# 917S001_ZHTH-010_-F.net
KiCad netlist of a schematic drawn in Altium Designer
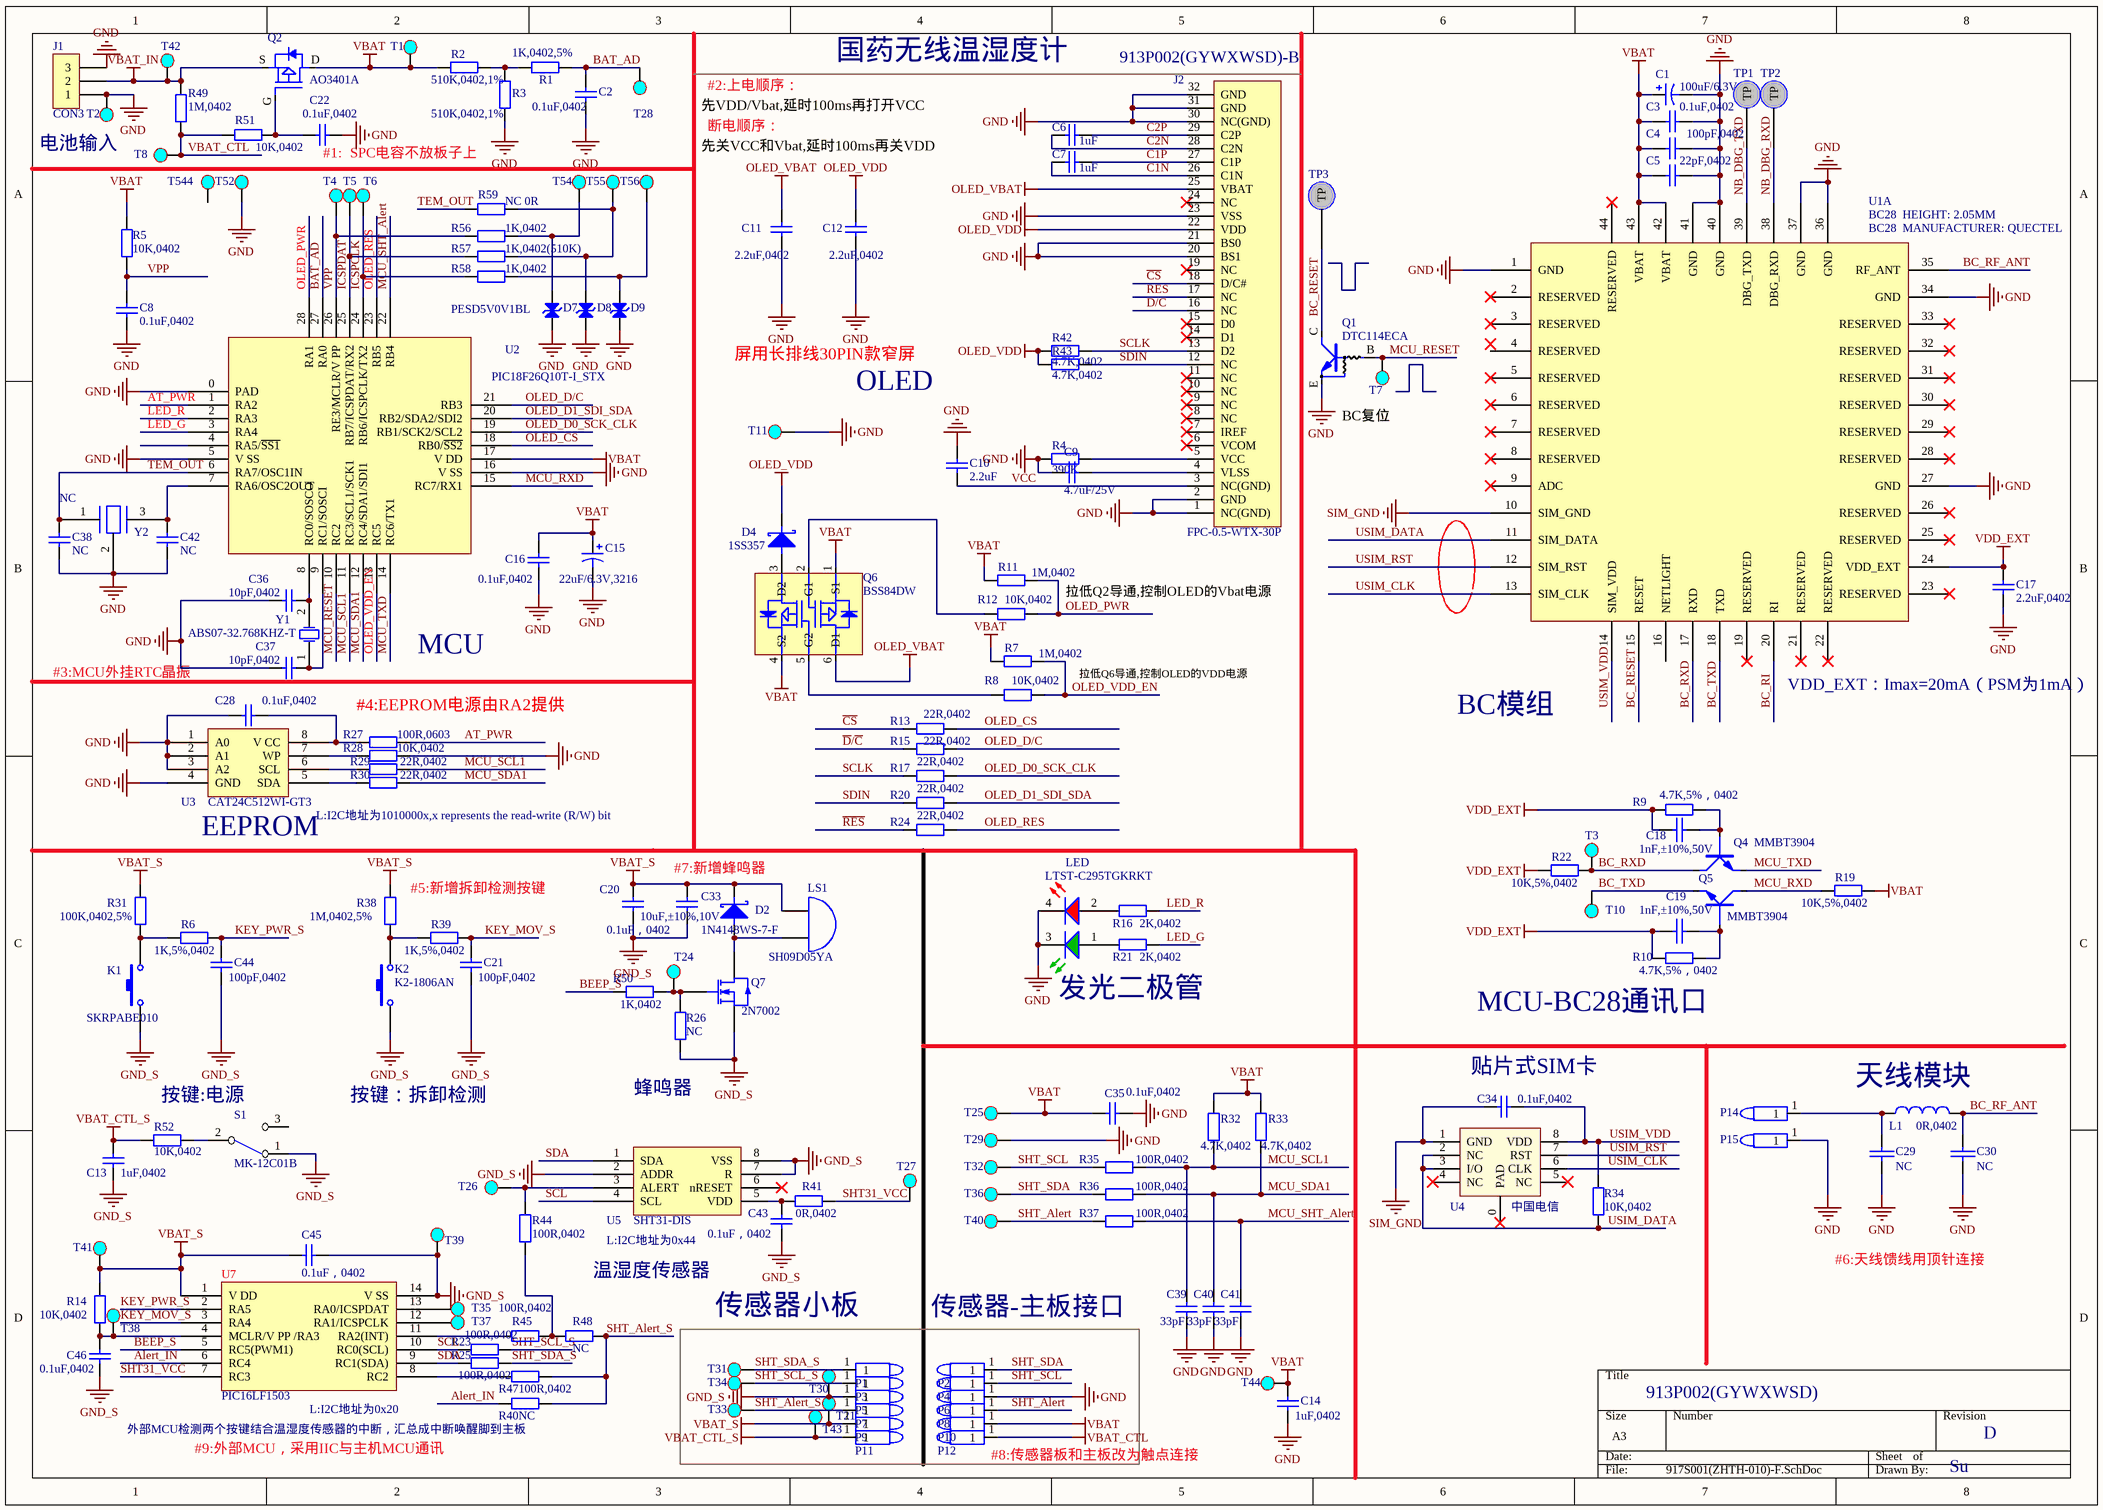
[diagram p0: 917S001(ZHTH-010)-F.SchDoc]

(export (version "E")
  (design (tool "Eeschema 10.0.6"))
  (components
    (comp (ref "C1")
      (value "100uF/6.3V")
      (footprint "3528")
      (description "Polarized Capacitor (Axial)")
      (fields (field (name "PUBLISHER") "Altium Limited"))
      (libsource (lib "JL_SCH") (part "Cap Pol2"))
    )
    (comp (ref "C2")
      (value "0.1uF,0402")
      (footprint "0402")
      (description "Capacitor")
      (fields (field (name "PUBLISHER") "Altium Limited"))
      (libsource (lib "*") (part "Cap"))
    )
    (comp (ref "C3")
      (value "0.1uF,0402")
      (footprint "0402")
      (description "Capacitor")
      (fields (field (name "PUBLISHER") "Altium Limited"))
      (libsource (lib "*") (part "Cap"))
    )
    (comp (ref "C4")
      (value "100pF,0402")
      (footprint "0402")
      (description "Capacitor")
      (fields (field (name "PUBLISHER") "Altium Limited"))
      (libsource (lib "*") (part "Cap"))
    )
    (comp (ref "C5")
      (value "22pF,0402")
      (footprint "0402")
      (description "Capacitor")
      (fields (field (name "PUBLISHER") "Altium Limited"))
      (libsource (lib "*") (part "Cap"))
    )
    (comp (ref "C6")
      (value "1uF")
      (footprint "0402")
      (description "Capacitor")
      (libsource (lib "JL_SCH") (part "Cap"))
    )
    (comp (ref "C7")
      (value "1uF")
      (footprint "0402")
      (description "Capacitor")
      (libsource (lib "JL_SCH") (part "Cap"))
    )
    (comp (ref "C8")
      (value "0.1uF,0402")
      (footprint "0402")
      (description "Capacitor")
      (fields (field (name "PUBLISHER") "Altium Limited"))
      (libsource (lib "*") (part "Cap"))
    )
    (comp (ref "C9")
      (value "4.7uF/25V")
      (footprint "0805")
      (description "Capacitor")
      (libsource (lib "JL_SCH") (part "Cap"))
    )
    (comp (ref "C10")
      (value "2.2uF")
      (footprint "0402")
      (description "Capacitor")
      (libsource (lib "JL_SCH") (part "Cap"))
    )
    (comp (ref "C11")
      (value "2.2uF,0402")
      (footprint "0402")
      (description "Capacitor")
      (libsource (lib "JL_SCH") (part "Cap"))
    )
    (comp (ref "C12")
      (value "2.2uF,0402")
      (footprint "0402")
      (description "Capacitor")
      (libsource (lib "JL_SCH") (part "Cap"))
    )
    (comp (ref "C13")
      (value "1uF,0402")
      (footprint "0402")
      (description "Capacitor")
      (libsource (lib "Miscellaneous Devices") (part "Cap"))
    )
    (comp (ref "C14")
      (value "1uF,0402")
      (footprint "0402")
      (description "Capacitor")
      (libsource (lib "Miscellaneous Devices") (part "Cap"))
    )
    (comp (ref "C15")
      (value "22uF/6.3V,3216")
      (footprint "3216")
      (description "Polarized Capacitor (Axial)")
      (fields (field (name "PUBLISHER") "Altium Limited"))
      (libsource (lib "JL_SCH") (part "Cap Pol2"))
    )
    (comp (ref "C16")
      (value "0.1uF,0402")
      (footprint "0402")
      (description "Capacitor")
      (fields (field (name "PUBLISHER") "Altium Limited"))
      (libsource (lib "*") (part "Cap"))
    )
    (comp (ref "C17")
      (value "2.2uF,0402")
      (footprint "0402")
      (description "Capacitor")
      (fields (field (name "PUBLISHER") "Altium Limited"))
      (libsource (lib "*") (part "Cap"))
    )
    (comp (ref "C18")
      (value "1nF,±10%,50V")
      (footprint "0402")
      (description "Capacitor")
      (fields
        (field (name "MANUFACTURER") "Generic Components")
        (field (name "PUBLISHER") "Altium Hobart Technology Centre")
      )
      (libsource (lib "LSD_DXPlib") (part "Cap"))
    )
    (comp (ref "C19")
      (value "1nF,±10%,50V")
      (footprint "0402")
      (description "Capacitor")
      (fields
        (field (name "MANUFACTURER") "Generic Components")
        (field (name "PUBLISHER") "Altium Hobart Technology Centre")
      )
      (libsource (lib "LSD_DXPlib") (part "Cap"))
    )
    (comp (ref "C20")
      (value "0.1uF，0402")
      (footprint "0402")
      (description "Capacitor")
      (fields (field (name "PUBLISHER") "Altium Limited"))
      (libsource (lib "*") (part "Cap"))
    )
    (comp (ref "C21")
      (value "100pF,0402")
      (footprint "0402")
      (description "Capacitor")
      (libsource (lib "Miscellaneous Devices") (part "Cap"))
    )
    (comp (ref "C22")
      (value "0.1uF,0402")
      (footprint "0402")
      (description "Capacitor")
      (fields (field (name "PUBLISHER") "Altium Limited"))
      (libsource (lib "*") (part "Cap"))
    )
    (comp (ref "C28")
      (value "0.1uF,0402")
      (footprint "0402")
      (description "Capacitor")
      (fields (field (name "PUBLISHER") "Altium Limited"))
      (libsource (lib "*") (part "Cap"))
    )
    (comp (ref "C29")
      (value "NC")
      (footprint "0402")
      (description "Capacitor")
      (fields
        (field (name "MANUFACTURER") "Generic Components")
        (field (name "PUBLISHER") "Altium Hobart Technology Centre")
      )
      (libsource (lib "LSD_DXPlib") (part "Cap"))
    )
    (comp (ref "C30")
      (value "NC")
      (footprint "0402")
      (description "Capacitor")
      (fields
        (field (name "MANUFACTURER") "Generic Components")
        (field (name "PUBLISHER") "Altium Hobart Technology Centre")
      )
      (libsource (lib "LSD_DXPlib") (part "Cap"))
    )
    (comp (ref "C33")
      (value "10uF,±10%,10V")
      (footprint "0805")
      (description "Capacitor")
      (libsource (lib "JL_SCH") (part "Cap"))
    )
    (comp (ref "C34")
      (value "0.1uF,0402")
      (footprint "0402")
      (description "Capacitor")
      (fields (field (name "PUBLISHER") "Altium Limited"))
      (libsource (lib "Miscellaneous Devices") (part "Cap"))
    )
    (comp (ref "C35")
      (value "0.1uF,0402")
      (footprint "0402")
      (description "Capacitor")
      (fields (field (name "PUBLISHER") "Altium Limited"))
      (libsource (lib "*") (part "Cap"))
    )
    (comp (ref "C36")
      (value "10pF,0402")
      (footprint "0402")
      (description "Capacitor")
      (fields (field (name "PUBLISHER") "Altium Limited"))
      (libsource (lib "*") (part "Cap"))
    )
    (comp (ref "C37")
      (value "10pF,0402")
      (footprint "0402")
      (description "Capacitor")
      (fields (field (name "PUBLISHER") "Altium Limited"))
      (libsource (lib "*") (part "Cap"))
    )
    (comp (ref "C38")
      (value "NC")
      (footprint "0402")
      (description "Capacitor")
      (fields (field (name "PUBLISHER") "Altium Limited"))
      (libsource (lib "*") (part "Cap"))
    )
    (comp (ref "C39")
      (value "33pF")
      (footprint "0402")
      (description "Capacitor")
      (fields (field (name "PUBLISHER") "Altium Limited"))
      (libsource (lib "Miscellaneous Devices") (part "Cap"))
    )
    (comp (ref "C40")
      (value "33pF")
      (footprint "0402")
      (description "Capacitor")
      (fields (field (name "PUBLISHER") "Altium Limited"))
      (libsource (lib "Miscellaneous Devices") (part "Cap"))
    )
    (comp (ref "C41")
      (value "33pF")
      (footprint "0402")
      (description "Capacitor")
      (fields (field (name "PUBLISHER") "Altium Limited"))
      (libsource (lib "Miscellaneous Devices") (part "Cap"))
    )
    (comp (ref "C42")
      (value "NC")
      (footprint "0402")
      (description "Capacitor")
      (fields (field (name "PUBLISHER") "Altium Limited"))
      (libsource (lib "*") (part "Cap"))
    )
    (comp (ref "C43")
      (value "0.1uF，0402")
      (footprint "0402")
      (description "Capacitor")
      (fields (field (name "PUBLISHER") "Altium Limited"))
      (libsource (lib "*") (part "Cap"))
    )
    (comp (ref "C44")
      (value "100pF,0402")
      (footprint "0402")
      (description "Capacitor")
      (libsource (lib "Miscellaneous Devices") (part "Cap"))
    )
    (comp (ref "C45")
      (value "0.1uF，0402")
      (footprint "0402")
      (description "Capacitor")
      (fields (field (name "PUBLISHER") "Altium Limited"))
      (libsource (lib "*") (part "Cap"))
    )
    (comp (ref "C46")
      (value "0.1uF,0402")
      (footprint "0402")
      (description "Capacitor")
      (fields (field (name "PUBLISHER") "Altium Limited"))
      (libsource (lib "*") (part "Cap"))
    )
    (comp (ref "D2")
      (value "1N4148WS-7-F")
      (footprint "SOD-323")
      (description "Schottky Diode")
      (libsource (lib "Schlib1") (part "DIODE SCHOTTKY"))
    )
    (comp (ref "D4")
      (value "1SS357")
      (footprint "SOD-323")
      (description "Schottky Diode")
      (libsource (lib "Schlib1") (part "DIODE SCHOTTKY"))
    )
    (comp (ref "D7")
      (value "PESD5V0V1BL")
      (footprint "DFN1006")
      (description "TVS管")
      (libsource (lib "标准原理图库（特种板）") (part "DIODE TVS"))
    )
    (comp (ref "D8")
      (value "PESD5V0V1BL")
      (footprint "DFN1006")
      (description "TVS管")
      (libsource (lib "标准原理图库（特种板）") (part "DIODE TVS"))
    )
    (comp (ref "D9")
      (value "PESD5V0V1BL")
      (footprint "DFN1006")
      (description "TVS管")
      (libsource (lib "标准原理图库（特种板）") (part "DIODE TVS"))
    )
    (comp (ref "J1")
      (value "CON3")
      (footprint "JVT1125W4T-02SN-S")
      (description "Connector")
      (libsource (lib "标准原理图库（特种板）") (part "CON3"))
    )
    (comp (ref "J2")
      (value "FPC-0.5-WTX-30P")
      (footprint "FPC-wo-0.5-30 - f")
      (libsource (lib "标准原理图库（特种板）") (part "Header 32-2"))
    )
    (comp (ref "K1")
      (value "SKRPABE010")
      (footprint "SKRPABE010")
      (description "Switch")
      (fields (field (name "PUBLISHER") "Altium Limited"))
      (libsource (lib "Miscellaneous Devices") (part "SW-PB"))
    )
    (comp (ref "K2")
      (value "K2-1806AN")
      (footprint "K2-1806AN")
      (description "Switch")
      (fields (field (name "PUBLISHER") "Altium Limited"))
      (libsource (lib "Miscellaneous Devices") (part "SW-PB"))
    )
    (comp (ref "L1")
      (value "0R,0402")
      (footprint "0402")
      (description "Inductor")
      (fields (field (name "PUBLISHER") "Altium Limited"))
      (libsource (lib "Miscellaneous Devices") (part "Inductor"))
    )
    (comp (ref "LED")
      (value "LTST-C295TGKRKT")
      (footprint "LTST-295T")
      (libsource (lib "Schlib1") (part "LTST-C295TGKRKT"))
    )
    (comp (ref "LS1")
      (value "SH09D05YA")
      (footprint "SH09D05YA")
      (description "Electrical Bell")
      (fields (field (name "PUBLISHER") "Altium Limited"))
      (libsource (lib "Miscellaneous Devices") (part "Bell"))
    )
    (comp (ref "P1")
      (value "TZ-650B01")
      (footprint "POGOPAD")
      (libsource (lib "标准原理图库（特种板）") (part "POGOPIN"))
    )
    (comp (ref "P2")
      (value "TZ-650B01")
      (footprint "POGOPAD")
      (libsource (lib "标准原理图库（特种板）") (part "POGOPIN"))
    )
    (comp (ref "P3")
      (value "TZ-650B01")
      (footprint "POGOPAD")
      (libsource (lib "标准原理图库（特种板）") (part "POGOPIN"))
    )
    (comp (ref "P4")
      (value "TZ-650B01")
      (footprint "POGOPAD")
      (libsource (lib "标准原理图库（特种板）") (part "POGOPIN"))
    )
    (comp (ref "P5")
      (value "TZ-650B01")
      (footprint "POGOPAD")
      (libsource (lib "标准原理图库（特种板）") (part "POGOPIN"))
    )
    (comp (ref "P6")
      (value "TZ-650B01")
      (footprint "POGOPAD")
      (libsource (lib "标准原理图库（特种板）") (part "POGOPIN"))
    )
    (comp (ref "P7")
      (value "TZ-650B01")
      (footprint "POGOPAD")
      (libsource (lib "标准原理图库（特种板）") (part "POGOPIN"))
    )
    (comp (ref "P8")
      (value "TZ-650B01")
      (footprint "POGOPAD")
      (libsource (lib "标准原理图库（特种板）") (part "POGOPIN"))
    )
    (comp (ref "P9")
      (value "TZ-650B01")
      (footprint "POGOPAD")
      (libsource (lib "标准原理图库（特种板）") (part "POGOPIN"))
    )
    (comp (ref "P10")
      (value "TZ-650B01")
      (footprint "POGOPAD")
      (libsource (lib "标准原理图库（特种板）") (part "POGOPIN"))
    )
    (comp (ref "P11")
      (value "TZ-650B01")
      (footprint "POGOPAD")
      (libsource (lib "标准原理图库（特种板）") (part "POGOPIN"))
    )
    (comp (ref "P12")
      (value "TZ-650B01")
      (footprint "POGOPAD")
      (libsource (lib "标准原理图库（特种板）") (part "POGOPIN"))
    )
    (comp (ref "P14")
      (value "TZ-650B01")
      (footprint "POGOPAD")
      (libsource (lib "标准原理图库（特种板）") (part "POGOPIN"))
    )
    (comp (ref "P15")
      (value "TZ-650B01")
      (footprint "POGOPAD")
      (libsource (lib "标准原理图库（特种板）") (part "POGOPIN"))
    )
    (comp (ref "Q1")
      (value "DTC114ECA")
      (footprint "SOT-23(BEC)")
      (description "三极管")
      (libsource (lib "标准原理图库（特种板）") (part "PDTC114ET"))
    )
    (comp (ref "Q2")
      (value "AO3401A")
      (footprint "SOT-23 (GSD)-L")
      (description "MOSFET")
      (libsource (lib "Blueway-SCH LIB") (part "MOS P"))
    )
    (comp (ref "Q4")
      (value "MMBT3904")
      (footprint "SOT-23(BEC)")
      (description "三极管")
      (libsource (lib "标准原理图库（特种板）") (part "NPN"))
    )
    (comp (ref "Q5")
      (value "MMBT3904")
      (footprint "SOT-23(BEC)")
      (description "三极管")
      (libsource (lib "标准原理图库（特种板）") (part "NPN"))
    )
    (comp (ref "Q6")
      (value "BSS84DW")
      (footprint "SOT-363")
      (description "MOSFET")
      (libsource (lib "标准原理图库（特种板）") (part "MOS D-P(SOT363)"))
    )
    (comp (ref "Q7") (value "2N7002") (footprint "SOT-23") (libsource (lib "Schlib1") (part "N-MOSFET")))
    (comp (ref "R1")
      (value "1K,0402,5%")
      (footprint "0402")
      (description "Resistor")
      (fields (field (name "PUBLISHER") "Altium Limited"))
      (libsource (lib "") (part "Res2_2"))
    )
    (comp (ref "R2")
      (value "510K,0402,1%")
      (footprint "0402")
      (description "Resistor")
      (fields (field (name "PUBLISHER") "Altium Limited"))
      (libsource (lib "") (part "Res2_2"))
    )
    (comp (ref "R3")
      (value "510K,0402,1%")
      (footprint "0402")
      (description "Resistor")
      (fields (field (name "PUBLISHER") "Altium Limited"))
      (libsource (lib "") (part "Res2_3"))
    )
    (comp (ref "R4")
      (value "390K")
      (footprint "0603")
      (description "Resistor")
      (libsource (lib "altium-import") (part "root_2__Miscellaneous Devices.IntLib"))
    )
    (comp (ref "R5")
      (value "10K,0402")
      (footprint "0402")
      (description "Resistor")
      (fields (field (name "PUBLISHER") "Altium Limited"))
      (libsource (lib "") (part "Res2_4"))
    )
    (comp (ref "R6")
      (value "1K,5%,0402")
      (footprint "0402")
      (description "Resistor")
      (fields (field (name "PUBLISHER") "Altium Limited"))
      (libsource (lib "Miscellaneous Devices") (part "Res2"))
    )
    (comp (ref "R7")
      (value "1M,0402")
      (footprint "0402")
      (description "Resistor")
      (fields (field (name "PUBLISHER") "Altium Limited"))
      (libsource (lib "") (part "Res2_2"))
    )
    (comp (ref "R8")
      (value "10K,0402")
      (footprint "0402")
      (description "Resistor")
      (fields (field (name "PUBLISHER") "Altium Limited"))
      (libsource (lib "") (part "Res2_1"))
    )
    (comp (ref "R9")
      (value "4.7K,5%，0402")
      (footprint "0402")
      (description "Resistor")
      (fields (field (name "PUBLISHER") "Altium Limited"))
      (libsource (lib "") (part "Res2_5"))
    )
    (comp (ref "R10")
      (value "4.7K,5%，0402")
      (footprint "0402")
      (description "Resistor")
      (fields (field (name "PUBLISHER") "Altium Limited"))
      (libsource (lib "") (part "Res2_1"))
    )
    (comp (ref "R11")
      (value "1M,0402")
      (footprint "0402")
      (description "Resistor")
      (fields (field (name "PUBLISHER") "Altium Limited"))
      (libsource (lib "") (part "Res2_2"))
    )
    (comp (ref "R12")
      (value "10K,0402")
      (footprint "0402")
      (description "Resistor")
      (fields (field (name "PUBLISHER") "Altium Limited"))
      (libsource (lib "") (part "Res2_1"))
    )
    (comp (ref "R13")
      (value "22R,0402")
      (footprint "0402")
      (description "Resistor")
      (fields (field (name "PUBLISHER") "Altium Limited"))
      (libsource (lib "") (part "Res2_1"))
    )
    (comp (ref "R14")
      (value "10K,0402")
      (footprint "0402")
      (description "Resistor")
      (fields (field (name "PUBLISHER") "Altium Limited"))
      (libsource (lib "") (part "Res2_5"))
    )
    (comp (ref "R15")
      (value "22R,0402")
      (footprint "0402")
      (description "Resistor")
      (fields (field (name "PUBLISHER") "Altium Limited"))
      (libsource (lib "") (part "Res2_1"))
    )
    (comp (ref "R16")
      (value "2K,0402")
      (footprint "0402")
      (description "Resistor")
      (fields (field (name "PUBLISHER") "Altium Limited"))
      (libsource (lib "Miscellaneous Devices") (part "Res2"))
    )
    (comp (ref "R17")
      (value "22R,0402")
      (footprint "0402")
      (description "Resistor")
      (fields (field (name "PUBLISHER") "Altium Limited"))
      (libsource (lib "") (part "Res2_1"))
    )
    (comp (ref "R19")
      (value "10K,5%,0402")
      (footprint "0402")
      (description "Resistor")
      (fields (field (name "PUBLISHER") "Altium Limited"))
      (libsource (lib "") (part "Res2_5"))
    )
    (comp (ref "R20")
      (value "22R,0402")
      (footprint "0402")
      (description "Resistor")
      (fields (field (name "PUBLISHER") "Altium Limited"))
      (libsource (lib "") (part "Res2_1"))
    )
    (comp (ref "R21")
      (value "2K,0402")
      (footprint "0402")
      (description "Resistor")
      (fields (field (name "PUBLISHER") "Altium Limited"))
      (libsource (lib "Miscellaneous Devices") (part "Res2"))
    )
    (comp (ref "R22")
      (value "10K,5%,0402")
      (footprint "0402")
      (description "Resistor")
      (fields (field (name "PUBLISHER") "Altium Limited"))
      (libsource (lib "") (part "Res2_5"))
    )
    (comp (ref "R23")
      (value "100R,0402")
      (footprint "0402")
      (description "Resistor")
      (fields (field (name "PUBLISHER") "Altium Limited"))
      (libsource (lib "Miscellaneous Devices") (part "Res2"))
    )
    (comp (ref "R24")
      (value "22R,0402")
      (footprint "0402")
      (description "Resistor")
      (fields (field (name "PUBLISHER") "Altium Limited"))
      (libsource (lib "") (part "Res2_1"))
    )
    (comp (ref "R25")
      (value "100R,0402")
      (footprint "0402")
      (description "Resistor")
      (fields (field (name "PUBLISHER") "Altium Limited"))
      (libsource (lib "Miscellaneous Devices") (part "Res2"))
    )
    (comp (ref "R26")
      (value "NC")
      (footprint "0402")
      (description "Resistor")
      (fields (field (name "PUBLISHER") "Altium Limited"))
      (libsource (lib "") (part "Res2_3"))
    )
    (comp (ref "R27")
      (value "100R,0603")
      (footprint "0402")
      (description "Resistor")
      (fields (field (name "PUBLISHER") "Altium Limited"))
      (libsource (lib "") (part "Res2_2"))
    )
    (comp (ref "R28")
      (value "10K,0402")
      (footprint "0402")
      (description "Resistor")
      (fields (field (name "PUBLISHER") "Altium Limited"))
      (libsource (lib "Miscellaneous Devices") (part "Res2"))
    )
    (comp (ref "R29")
      (value "22R,0402")
      (footprint "0402")
      (description "Resistor")
      (fields (field (name "PUBLISHER") "Altium Limited"))
      (libsource (lib "") (part "Res2_1"))
    )
    (comp (ref "R30")
      (value "22R,0402")
      (footprint "0402")
      (description "Resistor")
      (fields (field (name "PUBLISHER") "Altium Limited"))
      (libsource (lib "") (part "Res2_1"))
    )
    (comp (ref "R31")
      (value "100K,0402,5%")
      (footprint "0402")
      (description "Resistor")
      (libsource (lib "") (part "Res2_3"))
    )
    (comp (ref "R32")
      (value "4.7K,0402")
      (footprint "0402")
      (description "Resistor")
      (fields (field (name "PUBLISHER") "Altium Limited"))
      (libsource (lib "") (part "Res2_5"))
    )
    (comp (ref "R33")
      (value "4.7K,0402")
      (footprint "0402")
      (description "Resistor")
      (fields (field (name "PUBLISHER") "Altium Limited"))
      (libsource (lib "") (part "Res2_5"))
    )
    (comp (ref "R34")
      (value "10K,0402")
      (footprint "0402")
      (description "Resistor")
      (fields (field (name "PUBLISHER") "Altium Limited"))
      (libsource (lib "*") (part "Res2"))
    )
    (comp (ref "R35")
      (value "100R,0402")
      (footprint "0402")
      (description "Resistor")
      (fields (field (name "PUBLISHER") "Altium Limited"))
      (libsource (lib "") (part "Res2_1"))
    )
    (comp (ref "R36")
      (value "100R,0402")
      (footprint "0402")
      (description "Resistor")
      (fields (field (name "PUBLISHER") "Altium Limited"))
      (libsource (lib "") (part "Res2_1"))
    )
    (comp (ref "R37")
      (value "100R,0402")
      (footprint "0402")
      (description "Resistor")
      (fields (field (name "PUBLISHER") "Altium Limited"))
      (libsource (lib "") (part "Res2_1"))
    )
    (comp (ref "R38")
      (value "1M,0402,5%")
      (footprint "0402")
      (description "Resistor")
      (libsource (lib "") (part "Res2_3"))
    )
    (comp (ref "R39")
      (value "1K,5%,0402")
      (footprint "0402")
      (description "Resistor")
      (fields (field (name "PUBLISHER") "Altium Limited"))
      (libsource (lib "Miscellaneous Devices") (part "Res2"))
    )
    (comp (ref "R40")
      (value "NC")
      (footprint "0402")
      (description "Resistor")
      (fields (field (name "PUBLISHER") "Altium Limited"))
      (libsource (lib "Miscellaneous Devices") (part "Res2"))
    )
    (comp (ref "R41")
      (value "0R,0402")
      (footprint "0402")
      (description "Resistor")
      (fields (field (name "PUBLISHER") "Altium Limited"))
      (libsource (lib "Miscellaneous Devices") (part "Res2"))
    )
    (comp (ref "R42")
      (value "4.7K,0402")
      (footprint "0402")
      (description "Resistor")
      (fields (field (name "PUBLISHER") "Altium Limited"))
      (libsource (lib "") (part "Res2_6"))
    )
    (comp (ref "R43")
      (value "4.7K,0402")
      (footprint "0402")
      (description "Resistor")
      (fields (field (name "PUBLISHER") "Altium Limited"))
      (libsource (lib "") (part "Res2_6"))
    )
    (comp (ref "R44")
      (value "100R,0402")
      (footprint "0402")
      (description "Resistor")
      (fields (field (name "PUBLISHER") "Altium Limited"))
      (libsource (lib "") (part "Res2_1"))
    )
    (comp (ref "R45")
      (value "100R,0402")
      (footprint "0402")
      (description "Resistor")
      (fields (field (name "PUBLISHER") "Altium Limited"))
      (libsource (lib "Miscellaneous Devices") (part "Res2"))
    )
    (comp (ref "R47")
      (value "100R,0402")
      (footprint "0402")
      (description "Resistor")
      (fields (field (name "PUBLISHER") "Altium Limited"))
      (libsource (lib "Miscellaneous Devices") (part "Res2"))
    )
    (comp (ref "R48")
      (value "NC")
      (footprint "0402")
      (description "Resistor")
      (fields (field (name "PUBLISHER") "Altium Limited"))
      (libsource (lib "Miscellaneous Devices") (part "Res2"))
    )
    (comp (ref "R49")
      (value "1M,0402")
      (footprint "0402")
      (description "Resistor")
      (fields (field (name "PUBLISHER") "Altium Limited"))
      (libsource (lib "") (part "Res2_4"))
    )
    (comp (ref "R50")
      (value "1K,0402")
      (footprint "0402")
      (description "Resistor")
      (fields (field (name "PUBLISHER") "Altium Limited"))
      (libsource (lib "") (part "Res2_2"))
    )
    (comp (ref "R51")
      (value "10K,0402")
      (footprint "0402")
      (description "Resistor")
      (fields (field (name "PUBLISHER") "Altium Limited"))
      (libsource (lib "") (part "Res2_1"))
    )
    (comp (ref "R52")
      (value "10K,0402")
      (footprint "0402")
      (description "Resistor")
      (fields (field (name "PUBLISHER") "Altium Limited"))
      (libsource (lib "") (part "Res2_2"))
    )
    (comp (ref "R56")
      (value "1K,0402")
      (footprint "0402")
      (description "Resistor")
      (fields (field (name "PUBLISHER") "Altium Limited"))
      (libsource (lib "Miscellaneous Devices") (part "Res2"))
    )
    (comp (ref "R57")
      (value "1K,0402(510K)")
      (footprint "0402")
      (description "Resistor")
      (fields (field (name "PUBLISHER") "Altium Limited"))
      (libsource (lib "Miscellaneous Devices") (part "Res2"))
    )
    (comp (ref "R58")
      (value "1K,0402")
      (footprint "0402")
      (description "Resistor")
      (fields (field (name "PUBLISHER") "Altium Limited"))
      (libsource (lib "Miscellaneous Devices") (part "Res2"))
    )
    (comp (ref "R59")
      (value "NC 0R")
      (footprint "0402")
      (description "Resistor")
      (fields (field (name "PUBLISHER") "Altium Limited"))
      (libsource (lib "Miscellaneous Devices") (part "Res2"))
    )
    (comp (ref "S1")
      (value "MK-12C01B")
      (footprint "K3-1293S")
      (description "拨动开关")
      (libsource (lib "标准原理图库（特种板）") (part "SW SPDT"))
    )
    (comp (ref "T1")
      (value "TestPoints")
      (footprint "TestPoints")
      (libsource (lib "标准原理图库（特种板）") (part "TestPoints"))
    )
    (comp (ref "T2")
      (value "TestPoints")
      (footprint "TestPoints")
      (libsource (lib "标准原理图库（特种板）") (part "TestPoints"))
    )
    (comp (ref "T3")
      (value "TestPoints")
      (footprint "TestPoints-1.5")
      (libsource (lib "标准原理图库（特种板）") (part "TestPoints"))
    )
    (comp (ref "T4")
      (value "TestPoints")
      (footprint "TestPoints")
      (libsource (lib "标准原理图库（特种板）") (part "TestPoints"))
    )
    (comp (ref "T5")
      (value "TestPoints")
      (footprint "TestPoints")
      (libsource (lib "标准原理图库（特种板）") (part "TestPoints"))
    )
    (comp (ref "T6")
      (value "TestPoints")
      (footprint "TestPoints")
      (libsource (lib "标准原理图库（特种板）") (part "TestPoints"))
    )
    (comp (ref "T7")
      (value "TestPoints")
      (footprint "TestPoints-1.5")
      (libsource (lib "标准原理图库（特种板）") (part "TestPoints"))
    )
    (comp (ref "T8")
      (value "TestPoints")
      (footprint "TestPoints")
      (libsource (lib "标准原理图库（特种板）") (part "TestPoints"))
    )
    (comp (ref "T10")
      (value "TestPoints")
      (footprint "TestPoints-1.5")
      (libsource (lib "标准原理图库（特种板）") (part "TestPoints"))
    )
    (comp (ref "T11")
      (value "TestPoints")
      (footprint "TestPoints-1.5")
      (libsource (lib "标准原理图库（特种板）") (part "TestPoints"))
    )
    (comp (ref "T21")
      (value "TestPoints")
      (footprint "TestPoints-1.5")
      (libsource (lib "标准原理图库（特种板）") (part "TestPoints"))
    )
    (comp (ref "T24")
      (value "TestPoints")
      (footprint "TestPoints-1.5")
      (libsource (lib "标准原理图库（特种板）") (part "TestPoints"))
    )
    (comp (ref "T25")
      (value "TestPoints")
      (footprint "TestPoints-1.5")
      (libsource (lib "标准原理图库（特种板）") (part "TestPoints"))
    )
    (comp (ref "T26")
      (value "TestPoints")
      (footprint "TestPoints-1.5")
      (libsource (lib "标准原理图库（特种板）") (part "TestPoints"))
    )
    (comp (ref "T27")
      (value "TestPoints")
      (footprint "TestPoints-1.5")
      (libsource (lib "标准原理图库（特种板）") (part "TestPoints"))
    )
    (comp (ref "T28")
      (value "TestPoints")
      (footprint "TestPoints-1.5")
      (libsource (lib "标准原理图库（特种板）") (part "TestPoints"))
    )
    (comp (ref "T29")
      (value "TestPoints")
      (footprint "TestPoints-1.5")
      (libsource (lib "标准原理图库（特种板）") (part "TestPoints"))
    )
    (comp (ref "T30")
      (value "TestPoints")
      (footprint "TestPoints-1.5")
      (libsource (lib "标准原理图库（特种板）") (part "TestPoints"))
    )
    (comp (ref "T31")
      (value "TestPoints")
      (footprint "TestPoints-1.5")
      (libsource (lib "标准原理图库（特种板）") (part "TestPoints"))
    )
    (comp (ref "T32")
      (value "TestPoints")
      (footprint "TestPoints-1.5")
      (libsource (lib "标准原理图库（特种板）") (part "TestPoints"))
    )
    (comp (ref "T33")
      (value "TestPoints")
      (footprint "TestPoints-1.5")
      (libsource (lib "标准原理图库（特种板）") (part "TestPoints"))
    )
    (comp (ref "T34")
      (value "TestPoints")
      (footprint "TestPoints-1.5")
      (libsource (lib "标准原理图库（特种板）") (part "TestPoints"))
    )
    (comp (ref "T35")
      (value "TestPoints")
      (footprint "TestPoints-1.5")
      (libsource (lib "标准原理图库（特种板）") (part "TestPoints"))
    )
    (comp (ref "T36")
      (value "TestPoints")
      (footprint "TestPoints-1.5")
      (libsource (lib "标准原理图库（特种板）") (part "TestPoints"))
    )
    (comp (ref "T37")
      (value "TestPoints")
      (footprint "TestPoints-1.5")
      (libsource (lib "标准原理图库（特种板）") (part "TestPoints"))
    )
    (comp (ref "T38")
      (value "TestPoints")
      (footprint "TestPoints-1.5")
      (libsource (lib "标准原理图库（特种板）") (part "TestPoints"))
    )
    (comp (ref "T39")
      (value "TestPoints")
      (footprint "TestPoints-1.5")
      (libsource (lib "标准原理图库（特种板）") (part "TestPoints"))
    )
    (comp (ref "T40")
      (value "TestPoints")
      (footprint "TestPoints-1.5")
      (libsource (lib "标准原理图库（特种板）") (part "TestPoints"))
    )
    (comp (ref "T41")
      (value "TestPoints")
      (footprint "TestPoints-1.5")
      (libsource (lib "标准原理图库（特种板）") (part "TestPoints"))
    )
    (comp (ref "T42")
      (value "TestPoints")
      (footprint "TestPoints")
      (libsource (lib "标准原理图库（特种板）") (part "TestPoints"))
    )
    (comp (ref "T43")
      (value "TestPoints")
      (footprint "TestPoints-1.5")
      (libsource (lib "标准原理图库（特种板）") (part "TestPoints"))
    )
    (comp (ref "T44")
      (value "TestPoints")
      (footprint "TestPoints-1.5")
      (libsource (lib "标准原理图库（特种板）") (part "TestPoints"))
    )
    (comp (ref "T52")
      (value "TestPoints")
      (footprint "TestPoints")
      (libsource (lib "标准原理图库（特种板）") (part "TestPoints"))
    )
    (comp (ref "T54")
      (value "TestPoints")
      (footprint "TestPoints")
      (libsource (lib "标准原理图库（特种板）") (part "TestPoints"))
    )
    (comp (ref "T55")
      (value "TestPoints")
      (footprint "TestPoints")
      (libsource (lib "标准原理图库（特种板）") (part "TestPoints"))
    )
    (comp (ref "T56")
      (value "TestPoints")
      (footprint "TestPoints")
      (libsource (lib "标准原理图库（特种板）") (part "TestPoints"))
    )
    (comp (ref "T544")
      (value "TestPoints")
      (footprint "TestPoints")
      (libsource (lib "标准原理图库（特种板）") (part "TestPoints"))
    )
    (comp (ref "TP1")
      (value "TP1")
      (footprint "TestPoints-1.5")
      (libsource (lib "Schlib1") (part "Component_2"))
    )
    (comp (ref "TP2")
      (value "TP2")
      (footprint "TestPoints-1.5")
      (libsource (lib "Schlib1") (part "Component_2"))
    )
    (comp (ref "TP3")
      (value "TP2")
      (footprint "TestPoints-1.5")
      (libsource (lib "Schlib1") (part "Component_2"))
    )
    (comp (ref "U1")
      (value "BC28")
      (footprint "BC28")
      (fields
        (field (name "ALTIUM_VALUE") "BC28")
        (field (name "HEIGHT") "2.05MM")
        (field (name "MANUFACTURER") "QUECTEL")
      )
      (libsource (lib "Schlib1") (part "BC28"))
    )
    (comp (ref "U2")
      (value "PIC18F26Q10T-I_STX")
      (footprint "UQFN28(4x4)")
      (libsource (lib "BC28-test") (part "PIC16F15356"))
    )
    (comp (ref "U3")
      (value "CAT24C512WI-GT3")
      (footprint "SO8")
      (libsource (lib "Schlib1") (part "AT24C32D"))
    )
    (comp (ref "U4") (value "中国电信") (footprint "SMT_CARD") (libsource (lib "通讯器件") (part "QUAD_EUICC")))
    (comp (ref "U5")
      (value "SHT31-DIS")
      (footprint "DFN-8(2.5X2.5)")
      (libsource (lib "Schlib1") (part "SHT35"))
    )
    (comp (ref "U7")
      (value "PIC16LF1503")
      (footprint "SO14")
      (libsource (lib "标准原理图库（特种板）") (part "PIC16LF1503"))
    )
    (comp (ref "Y1")
      (value "ABS07-32.768KHZ-T")
      (footprint "XTAL3215")
      (description "Crystal Oscillator")
      (libsource (lib "Miscellaneous Devices") (part "XTAL"))
    )
    (comp (ref "Y2")
      (value "NC")
      (footprint "Y3215")
      (libsource (lib "MOVCAM_Sch_Lib 20131216") (part "CSTCE12M00G52-RO"))
    )
  )
  (nets
    (net (code "1") (name "/AT_PWR") (class "Default")
      (node (ref "R27") (pin "1") (pinfunction "1_1") (pintype "passive"))
      (node (ref "U2") (pin "1") (pinfunction "RA2_1") (pintype "passive"))
    )
    (net (code "2") (name "/Alert_IN") (class "Default")
      (node (ref "R40") (pin "1") (pinfunction "1_1") (pintype "passive"))
      (node (ref "U7") (pin "6") (pinfunction "RC4_6") (pintype "passive"))
    )
    (net (code "3") (name "/BAT_AD") (class "Default")
      (node (ref "C2") (pin "1") (pinfunction "1_1") (pintype "passive"))
      (node (ref "R1") (pin "1") (pinfunction "1_1") (pintype "passive"))
      (node (ref "T28") (pin "1") (pinfunction "1_1") (pintype "passive"))
      (node (ref "U2") (pin "27") (pinfunction "RA0_27") (pintype "passive"))
    )
    (net (code "4") (name "/BC_RESET") (class "Default")
      (node (ref "Q1") (pin "C") (pinfunction "c_C") (pintype "passive"))
      (node (ref "TP3") (pin "1") (pinfunction "TP_1") (pintype "passive"))
      (node (ref "U1") (pin "15") (pinfunction "RESET_15") (pintype "passive"))
    )
    (net (code "5") (name "/BC_RF_ANT") (class "Default")
      (node (ref "C30") (pin "2") (pinfunction "2_2") (pintype "passive"))
      (node (ref "L1") (pin "2") (pinfunction "2_2") (pintype "passive"))
      (node (ref "U1") (pin "35") (pinfunction "RF_ANT_35") (pintype "passive"))
    )
    (net (code "6") (name "/BC_RI") (class "Default")
      (node (ref "U1") (pin "20") (pinfunction "RI_20") (pintype "passive"))
    )
    (net (code "7") (name "/BC_RXD") (class "Default")
      (node (ref "Q4") (pin "C") (pinfunction "c_C") (pintype "passive"))
      (node (ref "R22") (pin "1") (pinfunction "1_1") (pintype "passive"))
      (node (ref "T3") (pin "1") (pinfunction "1_1") (pintype "passive"))
      (node (ref "U1") (pin "17") (pinfunction "RXD_17") (pintype "passive"))
    )
    (net (code "8") (name "/BC_TXD") (class "Default")
      (node (ref "Q5") (pin "E") (pinfunction "e_E") (pintype "passive"))
      (node (ref "T10") (pin "1") (pinfunction "1_1") (pintype "passive"))
      (node (ref "U1") (pin "18") (pinfunction "TXD_18") (pintype "passive"))
    )
    (net (code "9") (name "/BEEP_S") (class "Default")
      (node (ref "R50") (pin "2") (pinfunction "2_2") (pintype "passive"))
      (node (ref "U7") (pin "5") (pinfunction "RC5(PWM1)_5") (pintype "passive"))
    )
    (net (code "10") (name "/C1N") (class "Default")
      (node (ref "C7") (pin "2") (pinfunction "2_2") (pintype "passive"))
      (node (ref "J2") (pin "26") (pinfunction "C1N_26") (pintype "passive"))
    )
    (net (code "11") (name "/C1P") (class "Default")
      (node (ref "C7") (pin "1") (pinfunction "1_1") (pintype "passive"))
      (node (ref "J2") (pin "27") (pinfunction "C1P_27") (pintype "passive"))
    )
    (net (code "12") (name "/C2N") (class "Default")
      (node (ref "C6") (pin "2") (pinfunction "2_2") (pintype "passive"))
      (node (ref "J2") (pin "28") (pinfunction "C2N_28") (pintype "passive"))
    )
    (net (code "13") (name "/C2P") (class "Default")
      (node (ref "C6") (pin "1") (pinfunction "1_1") (pintype "passive"))
      (node (ref "J2") (pin "29") (pinfunction "C2P_29") (pintype "passive"))
    )
    (net (code "14") (name "/ICSPCLK") (class "Default")
      (node (ref "R58") (pin "1") (pinfunction "1_1") (pintype "passive"))
      (node (ref "T6") (pin "1") (pinfunction "1_1") (pintype "passive"))
      (node (ref "U2") (pin "24") (pinfunction "RB6/ICSPCLK/TX2_24") (pintype "passive"))
    )
    (net (code "15") (name "/ICSPDAT") (class "Default")
      (node (ref "R57") (pin "1") (pinfunction "1_1") (pintype "passive"))
      (node (ref "T5") (pin "1") (pinfunction "1_1") (pintype "passive"))
      (node (ref "U2") (pin "25") (pinfunction "RB7/ICSPDAT/RX2_25") (pintype "passive"))
    )
    (net (code "16") (name "/KEY_MOV_S") (class "Default")
      (node (ref "C21") (pin "2") (pinfunction "2_2") (pintype "passive"))
      (node (ref "R39") (pin "2") (pinfunction "2_2") (pintype "passive"))
      (node (ref "U7") (pin "3") (pinfunction "RA4_3") (pintype "passive"))
    )
    (net (code "17") (name "/KEY_PWR_S") (class "Default")
      (node (ref "C44") (pin "2") (pinfunction "2_2") (pintype "passive"))
      (node (ref "R6") (pin "2") (pinfunction "2_2") (pintype "passive"))
      (node (ref "U7") (pin "2") (pinfunction "RA5_2") (pintype "passive"))
    )
    (net (code "18") (name "/LED_G") (class "Default")
      (node (ref "R21") (pin "2") (pinfunction "2_2") (pintype "passive"))
      (node (ref "U2") (pin "3") (pinfunction "RA4_3") (pintype "passive"))
    )
    (net (code "19") (name "/LED_R") (class "Default")
      (node (ref "R16") (pin "2") (pinfunction "2_2") (pintype "passive"))
      (node (ref "U2") (pin "2") (pinfunction "RA3_2") (pintype "passive"))
    )
    (net (code "20") (name "/MCU_RESET") (class "Default")
      (node (ref "Q1") (pin "B") (pinfunction "b_B") (pintype "passive"))
      (node (ref "T7") (pin "1") (pinfunction "1_1") (pintype "passive"))
      (node (ref "U2") (pin "10") (pinfunction "RC2_10") (pintype "passive"))
    )
    (net (code "21") (name "/MCU_RXD") (class "Default")
      (node (ref "Q5") (pin "C") (pinfunction "c_C") (pintype "passive"))
      (node (ref "R19") (pin "2") (pinfunction "2_2") (pintype "passive"))
      (node (ref "U2") (pin "15") (pinfunction "RC7/RX1_15") (pintype "passive"))
    )
    (net (code "22") (name "/MCU_SCL1") (class "Default")
      (node (ref "C39") (pin "2") (pinfunction "2_2") (pintype "passive"))
      (node (ref "R29") (pin "2") (pinfunction "2_2") (pintype "passive"))
      (node (ref "R32") (pin "2") (pinfunction "2_2") (pintype "passive"))
      (node (ref "R35") (pin "2") (pinfunction "2_2") (pintype "passive"))
      (node (ref "U2") (pin "11") (pinfunction "RC3/SCL1/SCK1_11") (pintype "passive"))
    )
    (net (code "23") (name "/MCU_SDA1") (class "Default")
      (node (ref "C40") (pin "2") (pinfunction "2_2") (pintype "passive"))
      (node (ref "R30") (pin "2") (pinfunction "2_2") (pintype "passive"))
      (node (ref "R33") (pin "2") (pinfunction "2_2") (pintype "passive"))
      (node (ref "R36") (pin "2") (pinfunction "2_2") (pintype "passive"))
      (node (ref "U2") (pin "12") (pinfunction "RC4/SDA1/SDI1_12") (pintype "passive"))
    )
    (net (code "24") (name "/MCU_SHT_Alert") (class "Default")
      (node (ref "C41") (pin "2") (pinfunction "2_2") (pintype "passive"))
      (node (ref "R37") (pin "2") (pinfunction "2_2") (pintype "passive"))
      (node (ref "U2") (pin "22") (pinfunction "RB4_22") (pintype "passive"))
    )
    (net (code "25") (name "/MCU_TXD") (class "Default")
      (node (ref "Q4") (pin "E") (pinfunction "e_E") (pintype "passive"))
      (node (ref "U2") (pin "14") (pinfunction "RC6/TX1_14") (pintype "passive"))
    )
    (net (code "26") (name "/NB_DBG_RXD") (class "Default")
      (node (ref "TP2") (pin "1") (pinfunction "TP_1") (pintype "passive"))
      (node (ref "U1") (pin "38") (pinfunction "DBG_RXD_38") (pintype "passive"))
    )
    (net (code "27") (name "/NB_DBG_TXD") (class "Default")
      (node (ref "TP1") (pin "1") (pinfunction "TP_1") (pintype "passive"))
      (node (ref "U1") (pin "39") (pinfunction "DBG_TXD_39") (pintype "passive"))
    )
    (net (code "28") (name "/OLED_CS") (class "Default")
      (node (ref "R13") (pin "2") (pinfunction "2_2") (pintype "passive"))
      (node (ref "U2") (pin "18") (pinfunction "RB0/~{SS2}_18") (pintype "passive"))
    )
    (net (code "29") (name "/OLED_D0_SCK_CLK") (class "Default")
      (node (ref "R17") (pin "2") (pinfunction "2_2") (pintype "passive"))
      (node (ref "U2") (pin "19") (pinfunction "RB1/SCK2/SCL2_19") (pintype "passive"))
    )
    (net (code "30") (name "/OLED_D1_SDI_SDA") (class "Default")
      (node (ref "R20") (pin "2") (pinfunction "2_2") (pintype "passive"))
      (node (ref "U2") (pin "20") (pinfunction "RB2/SDA2/SDI2_20") (pintype "passive"))
    )
    (net (code "31") (name "/OLED_D{slash}C") (class "Default")
      (node (ref "R15") (pin "2") (pinfunction "2_2") (pintype "passive"))
      (node (ref "U2") (pin "21") (pinfunction "RB3_21") (pintype "passive"))
    )
    (net (code "32") (name "/OLED_PWR") (class "Default")
      (node (ref "R11") (pin "1") (pinfunction "1_1") (pintype "passive"))
      (node (ref "R12") (pin "2") (pinfunction "2_2") (pintype "passive"))
      (node (ref "U2") (pin "28") (pinfunction "RA1_28") (pintype "passive"))
    )
    (net (code "33") (name "/OLED_RES") (class "Default")
      (node (ref "R24") (pin "2") (pinfunction "2_2") (pintype "passive"))
      (node (ref "U2") (pin "23") (pinfunction "RB5_23") (pintype "passive"))
    )
    (net (code "34") (name "/OLED_VDD_EN") (class "Default")
      (node (ref "R7") (pin "1") (pinfunction "1_1") (pintype "passive"))
      (node (ref "R8") (pin "2") (pinfunction "2_2") (pintype "passive"))
      (node (ref "U2") (pin "13") (pinfunction "RC5_13") (pintype "passive"))
    )
    (net (code "35") (name "/SCL") (class "Default")
      (node (ref "R23") (pin "1") (pinfunction "1_1") (pintype "passive"))
      (node (ref "U5") (pin "4") (pinfunction "SCL_4") (pintype "passive"))
      (node (ref "U7") (pin "10") (pinfunction "RC0(SCL)_10") (pintype "passive"))
    )
    (net (code "36") (name "/SCLK") (class "Default")
      (node (ref "J2") (pin "13") (pinfunction "D2_13") (pintype "passive"))
      (node (ref "R17") (pin "1") (pinfunction "1_1") (pintype "passive"))
      (node (ref "R42") (pin "2") (pinfunction "2_2") (pintype "passive"))
    )
    (net (code "37") (name "/SDA") (class "Default")
      (node (ref "R25") (pin "1") (pinfunction "1_1") (pintype "passive"))
      (node (ref "U5") (pin "1") (pinfunction "SDA_1") (pintype "passive"))
      (node (ref "U7") (pin "9") (pinfunction "RC1(SDA)_9") (pintype "passive"))
    )
    (net (code "38") (name "/SDIN") (class "Default")
      (node (ref "J2") (pin "12") (pinfunction "NC_12") (pintype "passive"))
      (node (ref "R20") (pin "1") (pinfunction "1_1") (pintype "passive"))
      (node (ref "R43") (pin "2") (pinfunction "2_2") (pintype "passive"))
    )
    (net (code "39") (name "/SHT31_VCC") (class "Default")
      (node (ref "R41") (pin "2") (pinfunction "2_2") (pintype "passive"))
      (node (ref "T27") (pin "1") (pinfunction "1_1") (pintype "passive"))
      (node (ref "U7") (pin "7") (pinfunction "RC3_7") (pintype "passive"))
    )
    (net (code "40") (name "/SHT_Alert") (class "Default")
      (node (ref "P8") (pin "1") (pinfunction "1_1") (pintype "passive"))
      (node (ref "R37") (pin "1") (pinfunction "1_1") (pintype "passive"))
      (node (ref "T40") (pin "1") (pinfunction "1_1") (pintype "passive"))
    )
    (net (code "41") (name "/SHT_Alert_S") (class "Default")
      (node (ref "P7") (pin "1") (pinfunction "1_1") (pintype "passive"))
      (node (ref "R40") (pin "2") (pinfunction "2_2") (pintype "passive"))
      (node (ref "R47") (pin "2") (pinfunction "2_2") (pintype "passive"))
      (node (ref "R48") (pin "2") (pinfunction "2_2") (pintype "passive"))
      (node (ref "T33") (pin "1") (pinfunction "1_1") (pintype "passive"))
    )
    (net (code "42") (name "/SHT_SCL") (class "Default")
      (node (ref "P4") (pin "1") (pinfunction "1_1") (pintype "passive"))
      (node (ref "R35") (pin "1") (pinfunction "1_1") (pintype "passive"))
      (node (ref "T32") (pin "1") (pinfunction "1_1") (pintype "passive"))
    )
    (net (code "43") (name "/SHT_SCL_S") (class "Default")
      (node (ref "P3") (pin "1") (pinfunction "1_1") (pintype "passive"))
      (node (ref "R23") (pin "2") (pinfunction "2_2") (pintype "passive"))
      (node (ref "T34") (pin "1") (pinfunction "1_1") (pintype "passive"))
    )
    (net (code "44") (name "/SHT_SDA") (class "Default")
      (node (ref "P2") (pin "1") (pinfunction "1_1") (pintype "passive"))
      (node (ref "R36") (pin "1") (pinfunction "1_1") (pintype "passive"))
      (node (ref "T36") (pin "1") (pinfunction "1_1") (pintype "passive"))
    )
    (net (code "45") (name "/SHT_SDA_S") (class "Default")
      (node (ref "P1") (pin "1") (pinfunction "1_1") (pintype "passive"))
      (node (ref "R25") (pin "2") (pinfunction "2_2") (pintype "passive"))
      (node (ref "T31") (pin "1") (pinfunction "1_1") (pintype "passive"))
    )
    (net (code "46") (name "/TEM_OUT") (class "Default")
      (node (ref "C38") (pin "1") (pinfunction "1_1") (pintype "passive"))
      (node (ref "R59") (pin "1") (pinfunction "1_1") (pintype "passive"))
      (node (ref "U2") (pin "6") (pinfunction "RA7/OSC1IN_6") (pintype "passive"))
      (node (ref "Y2") (pin "1") (pinfunction "1_1") (pintype "passive"))
    )
    (net (code "47") (name "/USIM_CLK") (class "Default")
      (node (ref "U1") (pin "13") (pinfunction "SIM_CLK_13") (pintype "passive"))
      (node (ref "U4") (pin "6") (pinfunction "CLK_6") (pintype "passive"))
    )
    (net (code "48") (name "/USIM_DATA") (class "Default")
      (node (ref "R34") (pin "1") (pinfunction "1_1") (pintype "passive"))
      (node (ref "U1") (pin "11") (pinfunction "SIM_DATA_11") (pintype "passive"))
      (node (ref "U4") (pin "2") (pinfunction "NC_2") (pintype "passive"))
      (node (ref "U4") (pin "3") (pinfunction "I/O_3") (pintype "passive"))
    )
    (net (code "49") (name "/USIM_RST") (class "Default")
      (node (ref "U1") (pin "12") (pinfunction "SIM_RST_12") (pintype "passive"))
      (node (ref "U4") (pin "7") (pinfunction "RST_7") (pintype "passive"))
    )
    (net (code "50") (name "/USIM_VDD") (class "Default")
      (node (ref "C34") (pin "1") (pinfunction "1_1") (pintype "passive"))
      (node (ref "R34") (pin "2") (pinfunction "2_2") (pintype "passive"))
      (node (ref "U1") (pin "14") (pinfunction "SIM_VDD_14") (pintype "passive"))
      (node (ref "U4") (pin "8") (pinfunction "VDD_8") (pintype "passive"))
    )
    (net (code "51") (name "/VCC") (class "Default")
      (node (ref "C10") (pin "1") (pinfunction "1_1") (pintype "passive"))
      (node (ref "J2") (pin "3") (pinfunction "NC(GND)_3") (pintype "passive"))
    )
    (net (code "52") (name "/VPP") (class "Default")
      (node (ref "C8") (pin "1") (pinfunction "1_1") (pintype "passive"))
      (node (ref "R5") (pin "1") (pinfunction "1_1") (pintype "passive"))
      (node (ref "R56") (pin "1") (pinfunction "1_1") (pintype "passive"))
      (node (ref "T4") (pin "1") (pinfunction "1_1") (pintype "passive"))
      (node (ref "U2") (pin "26") (pinfunction "RE3/MCLR/V_PP_26") (pintype "passive"))
    )
    (net (code "53") (name "/~{CS}") (class "Default")
      (node (ref "J2") (pin "18") (pinfunction "D/C#_18") (pintype "passive"))
      (node (ref "R13") (pin "1") (pinfunction "1_1") (pintype "passive"))
    )
    (net (code "54") (name "/~{D}{slash}~{C}") (class "Default")
      (node (ref "J2") (pin "16") (pinfunction "NC_16") (pintype "passive"))
      (node (ref "R15") (pin "1") (pinfunction "1_1") (pintype "passive"))
    )
    (net (code "55") (name "/~{RES}") (class "Default")
      (node (ref "J2") (pin "17") (pinfunction "NC_17") (pintype "passive"))
      (node (ref "R24") (pin "1") (pinfunction "1_1") (pintype "passive"))
    )
    (net (code "56") (name "GND") (class "Default")
      (node (ref "C1") (pin "2") (pinfunction "2_2") (pintype "passive"))
      (node (ref "C10") (pin "2") (pinfunction "2_2") (pintype "passive"))
      (node (ref "C11") (pin "1") (pinfunction "1_1") (pintype "passive"))
      (node (ref "C12") (pin "1") (pinfunction "1_1") (pintype "passive"))
      (node (ref "C14") (pin "1") (pinfunction "1_1") (pintype "passive"))
      (node (ref "C15") (pin "2") (pinfunction "2_2") (pintype "passive"))
      (node (ref "C16") (pin "2") (pinfunction "2_2") (pintype "passive"))
      (node (ref "C17") (pin "1") (pinfunction "1_1") (pintype "passive"))
      (node (ref "C2") (pin "2") (pinfunction "2_2") (pintype "passive"))
      (node (ref "C22") (pin "2") (pinfunction "2_2") (pintype "passive"))
      (node (ref "C28") (pin "2") (pinfunction "2_2") (pintype "passive"))
      (node (ref "C29") (pin "1") (pinfunction "1_1") (pintype "passive"))
      (node (ref "C3") (pin "2") (pinfunction "2_2") (pintype "passive"))
      (node (ref "C30") (pin "1") (pinfunction "1_1") (pintype "passive"))
      (node (ref "C35") (pin "2") (pinfunction "2_2") (pintype "passive"))
      (node (ref "C36") (pin "1") (pinfunction "1_1") (pintype "passive"))
      (node (ref "C37") (pin "1") (pinfunction "1_1") (pintype "passive"))
      (node (ref "C38") (pin "2") (pinfunction "2_2") (pintype "passive"))
      (node (ref "C39") (pin "1") (pinfunction "1_1") (pintype "passive"))
      (node (ref "C4") (pin "2") (pinfunction "2_2") (pintype "passive"))
      (node (ref "C40") (pin "1") (pinfunction "1_1") (pintype "passive"))
      (node (ref "C41") (pin "1") (pinfunction "1_1") (pintype "passive"))
      (node (ref "C42") (pin "2") (pinfunction "2_2") (pintype "passive"))
      (node (ref "C5") (pin "2") (pinfunction "2_2") (pintype "passive"))
      (node (ref "C8") (pin "2") (pinfunction "2_2") (pintype "passive"))
      (node (ref "C9") (pin "2") (pinfunction "2_2") (pintype "passive"))
      (node (ref "D7") (pin "1") (pinfunction "1_1") (pintype "passive"))
      (node (ref "D8") (pin "1") (pinfunction "1_1") (pintype "passive"))
      (node (ref "D9") (pin "1") (pinfunction "1_1") (pintype "passive"))
      (node (ref "J1") (pin "1") (pinfunction "1_1") (pintype "passive"))
      (node (ref "J1") (pin "3") (pinfunction "3_3") (pintype "passive"))
      (node (ref "J2") (pin "1") (pinfunction "NC(GND)_1") (pintype "passive"))
      (node (ref "J2") (pin "2") (pinfunction "GND_2") (pintype "passive"))
      (node (ref "J2") (pin "20") (pinfunction "BS1_20") (pintype "passive"))
      (node (ref "J2") (pin "21") (pinfunction "BS0_21") (pintype "passive"))
      (node (ref "J2") (pin "23") (pinfunction "VSS_23") (pintype "passive"))
      (node (ref "J2") (pin "30") (pinfunction "NC(GND)_30") (pintype "passive"))
      (node (ref "J2") (pin "31") (pinfunction "GND_31") (pintype "passive"))
      (node (ref "J2") (pin "32") (pinfunction "GND_32") (pintype "passive"))
      (node (ref "LED") (pin "3") (pinfunction "K_3") (pintype "passive"))
      (node (ref "LED") (pin "4") (pinfunction "K_4") (pintype "passive"))
      (node (ref "P15") (pin "1") (pinfunction "1_1") (pintype "passive"))
      (node (ref "P6") (pin "1") (pinfunction "1_1") (pintype "passive"))
      (node (ref "Q1") (pin "E") (pinfunction "e_E") (pintype "passive"))
      (node (ref "R28") (pin "2") (pinfunction "2_2") (pintype "passive"))
      (node (ref "R3") (pin "2") (pinfunction "2_2") (pintype "passive"))
      (node (ref "R4") (pin "2") (pinfunction "2_2") (pintype "passive"))
      (node (ref "T11") (pin "1") (pinfunction "1_1") (pintype "passive"))
      (node (ref "T2") (pin "1") (pinfunction "1_1") (pintype "passive"))
      (node (ref "T29") (pin "1") (pinfunction "1_1") (pintype "passive"))
      (node (ref "T52") (pin "1") (pinfunction "1_1") (pintype "passive"))
      (node (ref "U1") (pin "1") (pinfunction "GND_1") (pintype "passive"))
      (node (ref "U1") (pin "27") (pinfunction "GND_27") (pintype "passive"))
      (node (ref "U1") (pin "34") (pinfunction "GND_34") (pintype "passive"))
      (node (ref "U1") (pin "36") (pinfunction "GND_36") (pintype "passive"))
      (node (ref "U1") (pin "37") (pinfunction "GND_37") (pintype "passive"))
      (node (ref "U1") (pin "40") (pinfunction "GND_40") (pintype "passive"))
      (node (ref "U1") (pin "41") (pinfunction "GND_41") (pintype "passive"))
      (node (ref "U2") (pin "0") (pinfunction "PAD_0") (pintype "passive"))
      (node (ref "U2") (pin "16") (pinfunction "V_SS_16") (pintype "passive"))
      (node (ref "U2") (pin "5") (pinfunction "V_SS_5") (pintype "passive"))
      (node (ref "U3") (pin "1") (pinfunction "A0_1") (pintype "passive"))
      (node (ref "U3") (pin "2") (pinfunction "A1_2") (pintype "passive"))
      (node (ref "U3") (pin "3") (pinfunction "A2_3") (pintype "passive"))
      (node (ref "U3") (pin "4") (pinfunction "GND_4") (pintype "passive"))
      (node (ref "Y2") (pin "2") (pinfunction "2_2") (pintype "passive"))
    )
    (net (code "57") (name "GND_S") (class "Default")
      (node (ref "C13") (pin "1") (pinfunction "1_1") (pintype "passive"))
      (node (ref "C20") (pin "2") (pinfunction "2_2") (pintype "passive"))
      (node (ref "C21") (pin "1") (pinfunction "1_1") (pintype "passive"))
      (node (ref "C33") (pin "2") (pinfunction "2_2") (pintype "passive"))
      (node (ref "C43") (pin "2") (pinfunction "2_2") (pintype "passive"))
      (node (ref "C44") (pin "1") (pinfunction "1_1") (pintype "passive"))
      (node (ref "C45") (pin "2") (pinfunction "2_2") (pintype "passive"))
      (node (ref "C46") (pin "2") (pinfunction "2_2") (pintype "passive"))
      (node (ref "K1") (pin "2") (pinfunction "2_2") (pintype "passive"))
      (node (ref "K2") (pin "1") (pinfunction "1_1") (pintype "passive"))
      (node (ref "P5") (pin "1") (pinfunction "1_1") (pintype "passive"))
      (node (ref "Q7") (pin "2") (pinfunction "S_2") (pintype "passive"))
      (node (ref "R26") (pin "2") (pinfunction "2_2") (pintype "passive"))
      (node (ref "S1") (pin "1") (pinfunction "NO_1") (pintype "passive"))
      (node (ref "T30") (pin "1") (pinfunction "1_1") (pintype "passive"))
      (node (ref "T39") (pin "1") (pinfunction "1_1") (pintype "passive"))
      (node (ref "U5") (pin "2") (pinfunction "ADDR_2") (pintype "passive"))
      (node (ref "U5") (pin "7") (pinfunction "R_7") (pintype "passive"))
      (node (ref "U5") (pin "8") (pinfunction "VSS_8") (pintype "passive"))
      (node (ref "U7") (pin "14") (pinfunction "V_SS_14") (pintype "passive"))
    )
    (net (code "58") (name "Net-(C22-Pad1)") (class "Default")
      (node (ref "C22") (pin "1") (pinfunction "1_1") (pintype "passive"))
      (node (ref "Q2") (pin "G") (pinfunction "G_G") (pintype "passive"))
      (node (ref "R51") (pin "2") (pinfunction "2_2") (pintype "passive"))
    )
    (net (code "59") (name "Net-(C29-Pad2)") (class "Default")
      (node (ref "C29") (pin "2") (pinfunction "2_2") (pintype "passive"))
      (node (ref "L1") (pin "1") (pinfunction "1_1") (pintype "passive"))
      (node (ref "P14") (pin "1") (pinfunction "1_1") (pintype "passive"))
    )
    (net (code "60") (name "Net-(D2-A)") (class "Default")
      (node (ref "D2") (pin "1") (pinfunction "A_1") (pintype "passive"))
      (node (ref "LS1") (pin "2") (pinfunction "B_2") (pintype "passive"))
      (node (ref "Q7") (pin "3") (pinfunction "D_3") (pintype "passive"))
    )
    (net (code "61") (name "Net-(D4-A)") (class "Default")
      (node (ref "D4") (pin "1") (pinfunction "A_1") (pintype "passive"))
      (node (ref "Q6") (pin "3") (pinfunction "D2_3") (pintype "passive"))
    )
    (net (code "62") (name "Net-(D7-Pad2)") (class "Default")
      (node (ref "D7") (pin "2") (pinfunction "2_2") (pintype "passive"))
      (node (ref "R56") (pin "2") (pinfunction "2_2") (pintype "passive"))
      (node (ref "T54") (pin "1") (pinfunction "1_1") (pintype "passive"))
    )
    (net (code "63") (name "Net-(D8-Pad2)") (class "Default")
      (node (ref "D8") (pin "2") (pinfunction "2_2") (pintype "passive"))
      (node (ref "R57") (pin "2") (pinfunction "2_2") (pintype "passive"))
      (node (ref "R59") (pin "2") (pinfunction "2_2") (pintype "passive"))
      (node (ref "T55") (pin "1") (pinfunction "1_1") (pintype "passive"))
    )
    (net (code "64") (name "Net-(D9-Pad2)") (class "Default")
      (node (ref "D9") (pin "2") (pinfunction "2_2") (pintype "passive"))
      (node (ref "R58") (pin "2") (pinfunction "2_2") (pintype "passive"))
      (node (ref "T56") (pin "1") (pinfunction "1_1") (pintype "passive"))
    )
    (net (code "65") (name "Net-(J2-VCC)") (class "Default")
      (node (ref "J2") (pin "5") (pinfunction "VCC_5") (pintype "passive"))
      (node (ref "R4") (pin "1") (pinfunction "1_1") (pintype "passive"))
    )
    (net (code "66") (name "Net-(J2-VLSS)") (class "Default")
      (node (ref "C9") (pin "1") (pinfunction "1_1") (pintype "passive"))
      (node (ref "J2") (pin "4") (pinfunction "VLSS_4") (pintype "passive"))
    )
    (net (code "67") (name "Net-(K1-Pad1)") (class "Default")
      (node (ref "K1") (pin "1") (pinfunction "1_1") (pintype "passive"))
      (node (ref "R31") (pin "2") (pinfunction "2_2") (pintype "passive"))
      (node (ref "R6") (pin "1") (pinfunction "1_1") (pintype "passive"))
    )
    (net (code "68") (name "Net-(K2-Pad2)") (class "Default")
      (node (ref "K2") (pin "2") (pinfunction "2_2") (pintype "passive"))
      (node (ref "R38") (pin "2") (pinfunction "2_2") (pintype "passive"))
      (node (ref "R39") (pin "1") (pinfunction "1_1") (pintype "passive"))
    )
    (net (code "69") (name "Net-(LED-A-Pad1)") (class "Default")
      (node (ref "LED") (pin "1") (pinfunction "A_1") (pintype "passive"))
      (node (ref "R21") (pin "1") (pinfunction "1_1") (pintype "passive"))
    )
    (net (code "70") (name "Net-(LED-A-Pad2)") (class "Default")
      (node (ref "LED") (pin "2") (pinfunction "A_2") (pintype "passive"))
      (node (ref "R16") (pin "1") (pinfunction "1_1") (pintype "passive"))
    )
    (net (code "71") (name "Net-(Q4-b)") (class "Default")
      (node (ref "C18") (pin "1") (pinfunction "1_1") (pintype "passive"))
      (node (ref "Q4") (pin "B") (pinfunction "b_B") (pintype "passive"))
      (node (ref "R9") (pin "1") (pinfunction "1_1") (pintype "passive"))
    )
    (net (code "72") (name "Net-(Q5-b)") (class "Default")
      (node (ref "C19") (pin "1") (pinfunction "1_1") (pintype "passive"))
      (node (ref "Q5") (pin "B") (pinfunction "b_B") (pintype "passive"))
      (node (ref "R10") (pin "2") (pinfunction "2_2") (pintype "passive"))
    )
    (net (code "73") (name "Net-(Q6-G1)") (class "Default")
      (node (ref "Q6") (pin "2") (pinfunction "G1_2") (pintype "passive"))
      (node (ref "R12") (pin "1") (pinfunction "1_1") (pintype "passive"))
    )
    (net (code "74") (name "Net-(Q6-G2)") (class "Default")
      (node (ref "Q6") (pin "5") (pinfunction "G2_5") (pintype "passive"))
      (node (ref "R8") (pin "1") (pinfunction "1_1") (pintype "passive"))
    )
    (net (code "75") (name "Net-(Q7-G)") (class "Default")
      (node (ref "Q7") (pin "1") (pinfunction "G_1") (pintype "passive"))
      (node (ref "R26") (pin "1") (pinfunction "1_1") (pintype "passive"))
      (node (ref "R50") (pin "1") (pinfunction "1_1") (pintype "passive"))
      (node (ref "T24") (pin "1") (pinfunction "1_1") (pintype "passive"))
    )
    (net (code "76") (name "Net-(R1-Pad2)") (class "Default")
      (node (ref "R1") (pin "2") (pinfunction "2_2") (pintype "passive"))
      (node (ref "R2") (pin "1") (pinfunction "1_1") (pintype "passive"))
      (node (ref "R3") (pin "1") (pinfunction "1_1") (pintype "passive"))
    )
    (net (code "77") (name "Net-(R44-Pad1)") (class "Default")
      (node (ref "R44") (pin "1") (pinfunction "1_1") (pintype "passive"))
      (node (ref "R45") (pin "2") (pinfunction "2_2") (pintype "passive"))
      (node (ref "R48") (pin "1") (pinfunction "1_1") (pintype "passive"))
    )
    (net (code "78") (name "Net-(S1-COMMON)") (class "Default")
      (node (ref "R52") (pin "1") (pinfunction "1_1") (pintype "passive"))
      (node (ref "S1") (pin "2") (pinfunction "COMMON_2") (pintype "passive"))
    )
    (net (code "79") (name "Net-(U2-RA6{slash}OSC2OUT)") (class "Default")
      (node (ref "C42") (pin "1") (pinfunction "1_1") (pintype "passive"))
      (node (ref "U2") (pin "7") (pinfunction "RA6/OSC2OUT_7") (pintype "passive"))
      (node (ref "Y2") (pin "3") (pinfunction "3_3") (pintype "passive"))
    )
    (net (code "80") (name "Net-(U2-RC0{slash}SOSCO)") (class "Default")
      (node (ref "C36") (pin "2") (pinfunction "2_2") (pintype "passive"))
      (node (ref "U2") (pin "8") (pinfunction "RC0/SOSCO_8") (pintype "passive"))
      (node (ref "Y1") (pin "2") (pinfunction "OSC2_2") (pintype "passive"))
    )
    (net (code "81") (name "Net-(U2-RC1{slash}SOSCI)") (class "Default")
      (node (ref "C37") (pin "2") (pinfunction "2_2") (pintype "passive"))
      (node (ref "U2") (pin "9") (pinfunction "RC1/SOSCI_9") (pintype "passive"))
      (node (ref "Y1") (pin "1") (pinfunction "OSC1_1") (pintype "passive"))
    )
    (net (code "82") (name "Net-(U3-SCL)") (class "Default")
      (node (ref "R29") (pin "1") (pinfunction "1_1") (pintype "passive"))
      (node (ref "U3") (pin "6") (pinfunction "SCL_6") (pintype "passive"))
    )
    (net (code "83") (name "Net-(U3-SDA)") (class "Default")
      (node (ref "R30") (pin "1") (pinfunction "1_1") (pintype "passive"))
      (node (ref "U3") (pin "5") (pinfunction "SDA_5") (pintype "passive"))
    )
    (net (code "84") (name "Net-(U3-V_CC)") (class "Default")
      (node (ref "C28") (pin "1") (pinfunction "1_1") (pintype "passive"))
      (node (ref "R27") (pin "2") (pinfunction "2_2") (pintype "passive"))
      (node (ref "U3") (pin "8") (pinfunction "V_CC_8") (pintype "passive"))
    )
    (net (code "85") (name "Net-(U3-WP)") (class "Default")
      (node (ref "R28") (pin "1") (pinfunction "1_1") (pintype "passive"))
      (node (ref "U3") (pin "7") (pinfunction "WP_7") (pintype "passive"))
    )
    (net (code "86") (name "Net-(U5-ALERT)") (class "Default")
      (node (ref "R44") (pin "2") (pinfunction "2_2") (pintype "passive"))
      (node (ref "T26") (pin "1") (pinfunction "1_1") (pintype "passive"))
      (node (ref "U5") (pin "3") (pinfunction "ALERT_3") (pintype "passive"))
    )
    (net (code "87") (name "Net-(U5-VDD)") (class "Default")
      (node (ref "C43") (pin "1") (pinfunction "1_1") (pintype "passive"))
      (node (ref "R41") (pin "1") (pinfunction "1_1") (pintype "passive"))
      (node (ref "U5") (pin "5") (pinfunction "VDD_5") (pintype "passive"))
    )
    (net (code "88") (name "Net-(U7-MCLR{slash}V_PP_{slash}RA3)") (class "Default")
      (node (ref "C46") (pin "1") (pinfunction "1_1") (pintype "passive"))
      (node (ref "R14") (pin "2") (pinfunction "2_2") (pintype "passive"))
      (node (ref "T38") (pin "1") (pinfunction "1_1") (pintype "passive"))
      (node (ref "U7") (pin "4") (pinfunction "MCLR/V_PP_/RA3_4") (pintype "passive"))
    )
    (net (code "89") (name "Net-(U7-RA0{slash}ICSPDAT)") (class "Default")
      (node (ref "T35") (pin "1") (pinfunction "1_1") (pintype "passive"))
      (node (ref "U7") (pin "13") (pinfunction "RA0/ICSPDAT_13") (pintype "passive"))
    )
    (net (code "90") (name "Net-(U7-RA1{slash}ICSPCLK)") (class "Default")
      (node (ref "T37") (pin "1") (pinfunction "1_1") (pintype "passive"))
      (node (ref "U7") (pin "12") (pinfunction "RA1/ICSPCLK_12") (pintype "passive"))
    )
    (net (code "91") (name "Net-(U7-RA2(INT))") (class "Default")
      (node (ref "R45") (pin "1") (pinfunction "1_1") (pintype "passive"))
      (node (ref "U7") (pin "11") (pinfunction "RA2(INT)_11") (pintype "passive"))
    )
    (net (code "92") (name "Net-(U7-RC2)") (class "Default")
      (node (ref "R47") (pin "1") (pinfunction "1_1") (pintype "passive"))
      (node (ref "U7") (pin "8") (pinfunction "RC2_8") (pintype "passive"))
    )
    (net (code "93") (name "OLED_VBAT") (class "Default")
      (node (ref "C11") (pin "2") (pinfunction "2_2") (pintype "passive"))
      (node (ref "J2") (pin "25") (pinfunction "VBAT_25") (pintype "passive"))
      (node (ref "Q6") (pin "6") (pinfunction "D1_6") (pintype "passive"))
    )
    (net (code "94") (name "OLED_VDD") (class "Default")
      (node (ref "C12") (pin "2") (pinfunction "2_2") (pintype "passive"))
      (node (ref "D4") (pin "2") (pinfunction "K_2") (pintype "passive"))
      (node (ref "J2") (pin "22") (pinfunction "VDD_22") (pintype "passive"))
      (node (ref "R42") (pin "1") (pinfunction "1_1") (pintype "passive"))
      (node (ref "R43") (pin "1") (pinfunction "1_1") (pintype "passive"))
    )
    (net (code "95") (name "SIM_GND") (class "Default")
      (node (ref "C34") (pin "2") (pinfunction "2_2") (pintype "passive"))
      (node (ref "U1") (pin "10") (pinfunction "SIM_GND_10") (pintype "passive"))
      (node (ref "U4") (pin "1") (pinfunction "GND_1") (pintype "passive"))
    )
    (net (code "96") (name "VBAT") (class "Default")
      (node (ref "C1") (pin "1") (pinfunction "1_1") (pintype "passive"))
      (node (ref "C14") (pin "2") (pinfunction "2_2") (pintype "passive"))
      (node (ref "C15") (pin "1") (pinfunction "1_1") (pintype "passive"))
      (node (ref "C16") (pin "1") (pinfunction "1_1") (pintype "passive"))
      (node (ref "C3") (pin "1") (pinfunction "1_1") (pintype "passive"))
      (node (ref "C35") (pin "1") (pinfunction "1_1") (pintype "passive"))
      (node (ref "C4") (pin "1") (pinfunction "1_1") (pintype "passive"))
      (node (ref "C5") (pin "1") (pinfunction "1_1") (pintype "passive"))
      (node (ref "P10") (pin "1") (pinfunction "1_1") (pintype "passive"))
      (node (ref "Q2") (pin "D") (pinfunction "D_D") (pintype "passive"))
      (node (ref "Q6") (pin "1") (pinfunction "S1_1") (pintype "passive"))
      (node (ref "Q6") (pin "4") (pinfunction "S2_4") (pintype "passive"))
      (node (ref "R11") (pin "2") (pinfunction "2_2") (pintype "passive"))
      (node (ref "R19") (pin "1") (pinfunction "1_1") (pintype "passive"))
      (node (ref "R2") (pin "2") (pinfunction "2_2") (pintype "passive"))
      (node (ref "R32") (pin "1") (pinfunction "1_1") (pintype "passive"))
      (node (ref "R33") (pin "1") (pinfunction "1_1") (pintype "passive"))
      (node (ref "R5") (pin "2") (pinfunction "2_2") (pintype "passive"))
      (node (ref "R7") (pin "2") (pinfunction "2_2") (pintype "passive"))
      (node (ref "T1") (pin "1") (pinfunction "1_1") (pintype "passive"))
      (node (ref "T25") (pin "1") (pinfunction "1_1") (pintype "passive"))
      (node (ref "T44") (pin "1") (pinfunction "1_1") (pintype "passive"))
      (node (ref "U1") (pin "42") (pinfunction "VBAT_42") (pintype "passive"))
      (node (ref "U1") (pin "43") (pinfunction "VBAT_43") (pintype "passive"))
      (node (ref "U2") (pin "17") (pinfunction "V_DD_17") (pintype "passive"))
    )
    (net (code "97") (name "VBAT_CTL") (class "Default")
      (node (ref "P12") (pin "1") (pinfunction "1_1") (pintype "passive"))
      (node (ref "R49") (pin "1") (pinfunction "1_1") (pintype "passive"))
      (node (ref "R51") (pin "1") (pinfunction "1_1") (pintype "passive"))
      (node (ref "T8") (pin "1") (pinfunction "1_1") (pintype "passive"))
    )
    (net (code "98") (name "VBAT_CTL_S") (class "Default")
      (node (ref "C13") (pin "2") (pinfunction "2_2") (pintype "passive"))
      (node (ref "P11") (pin "1") (pinfunction "1_1") (pintype "passive"))
      (node (ref "R52") (pin "2") (pinfunction "2_2") (pintype "passive"))
      (node (ref "T43") (pin "1") (pinfunction "1_1") (pintype "passive"))
    )
    (net (code "99") (name "VBAT_IN") (class "Default")
      (node (ref "J1") (pin "2") (pinfunction "2_2") (pintype "passive"))
      (node (ref "Q2") (pin "S") (pinfunction "S_S") (pintype "passive"))
      (node (ref "R49") (pin "2") (pinfunction "2_2") (pintype "passive"))
      (node (ref "T42") (pin "1") (pinfunction "1_1") (pintype "passive"))
    )
    (net (code "100") (name "VBAT_S") (class "Default")
      (node (ref "C20") (pin "1") (pinfunction "1_1") (pintype "passive"))
      (node (ref "C33") (pin "1") (pinfunction "1_1") (pintype "passive"))
      (node (ref "C45") (pin "1") (pinfunction "1_1") (pintype "passive"))
      (node (ref "D2") (pin "2") (pinfunction "K_2") (pintype "passive"))
      (node (ref "LS1") (pin "1") (pinfunction "A_1") (pintype "passive"))
      (node (ref "P9") (pin "1") (pinfunction "1_1") (pintype "passive"))
      (node (ref "R14") (pin "1") (pinfunction "1_1") (pintype "passive"))
      (node (ref "R31") (pin "1") (pinfunction "1_1") (pintype "passive"))
      (node (ref "R38") (pin "1") (pinfunction "1_1") (pintype "passive"))
      (node (ref "T21") (pin "1") (pinfunction "1_1") (pintype "passive"))
      (node (ref "T41") (pin "1") (pinfunction "1_1") (pintype "passive"))
      (node (ref "U7") (pin "1") (pinfunction "V_DD_1") (pintype "passive"))
    )
    (net (code "101") (name "VDD_EXT") (class "Default")
      (node (ref "C17") (pin "2") (pinfunction "2_2") (pintype "passive"))
      (node (ref "C18") (pin "2") (pinfunction "2_2") (pintype "passive"))
      (node (ref "C19") (pin "2") (pinfunction "2_2") (pintype "passive"))
      (node (ref "R10") (pin "1") (pinfunction "1_1") (pintype "passive"))
      (node (ref "R22") (pin "2") (pinfunction "2_2") (pintype "passive"))
      (node (ref "R9") (pin "2") (pinfunction "2_2") (pintype "passive"))
      (node (ref "U1") (pin "24") (pinfunction "VDD_EXT_24") (pintype "passive"))
    )
    (net (code "102") (name "unconnected-(J2-D0-Pad15)") (class "Default")
      (node (ref "J2") (pin "15") (pinfunction "D0_15") (pintype "passive+no_connect"))
    )
    (net (code "103") (name "unconnected-(J2-D1-Pad14)") (class "Default")
      (node (ref "J2") (pin "14") (pinfunction "D1_14") (pintype "passive+no_connect"))
    )
    (net (code "104") (name "unconnected-(J2-IREF-Pad7)") (class "Default")
      (node (ref "J2") (pin "7") (pinfunction "IREF_7") (pintype "passive+no_connect"))
    )
    (net (code "105") (name "unconnected-(J2-NC-Pad8)") (class "Default")
      (node (ref "J2") (pin "8") (pinfunction "NC_8") (pintype "passive+no_connect"))
    )
    (net (code "106") (name "unconnected-(J2-NC-Pad9)") (class "Default")
      (node (ref "J2") (pin "9") (pinfunction "NC_9") (pintype "passive+no_connect"))
    )
    (net (code "107") (name "unconnected-(J2-NC-Pad10)") (class "Default")
      (node (ref "J2") (pin "10") (pinfunction "NC_10") (pintype "passive+no_connect"))
    )
    (net (code "108") (name "unconnected-(J2-NC-Pad11)") (class "Default")
      (node (ref "J2") (pin "11") (pinfunction "NC_11") (pintype "passive+no_connect"))
    )
    (net (code "109") (name "unconnected-(J2-NC-Pad19)") (class "Default")
      (node (ref "J2") (pin "19") (pinfunction "NC_19") (pintype "passive+no_connect"))
    )
    (net (code "110") (name "unconnected-(J2-NC-Pad24)") (class "Default")
      (node (ref "J2") (pin "24") (pinfunction "NC_24") (pintype "passive+no_connect"))
    )
    (net (code "111") (name "unconnected-(J2-VCOM-Pad6)") (class "Default")
      (node (ref "J2") (pin "6") (pinfunction "VCOM_6") (pintype "passive+no_connect"))
    )
    (net (code "112") (name "unconnected-(S1-NO-Pad3)") (class "Default")
      (node (ref "S1") (pin "3") (pinfunction "NO_3") (pintype "passive"))
    )
    (net (code "113") (name "unconnected-(T544-Pad1)") (class "Default")
      (node (ref "T544") (pin "1") (pinfunction "1_1") (pintype "passive"))
    )
    (net (code "114") (name "unconnected-(U1A-ADC-Pad9)") (class "Default")
      (node (ref "U1") (pin "9") (pinfunction "ADC_9") (pintype "passive+no_connect"))
    )
    (net (code "115") (name "unconnected-(U1A-NETLIGHT-Pad16)") (class "Default")
      (node (ref "U1") (pin "16") (pinfunction "NETLIGHT_16") (pintype "passive"))
    )
    (net (code "116") (name "unconnected-(U1A-RESERVED-Pad2)") (class "Default")
      (node (ref "U1") (pin "2") (pinfunction "RESERVED_2") (pintype "passive+no_connect"))
    )
    (net (code "117") (name "unconnected-(U1A-RESERVED-Pad3)") (class "Default")
      (node (ref "U1") (pin "3") (pinfunction "RESERVED_3") (pintype "passive+no_connect"))
    )
    (net (code "118") (name "unconnected-(U1A-RESERVED-Pad4)") (class "Default")
      (node (ref "U1") (pin "4") (pinfunction "RESERVED_4") (pintype "passive"))
    )
    (net (code "119") (name "unconnected-(U1A-RESERVED-Pad5)") (class "Default")
      (node (ref "U1") (pin "5") (pinfunction "RESERVED_5") (pintype "passive+no_connect"))
    )
    (net (code "120") (name "unconnected-(U1A-RESERVED-Pad6)") (class "Default")
      (node (ref "U1") (pin "6") (pinfunction "RESERVED_6") (pintype "passive+no_connect"))
    )
    (net (code "121") (name "unconnected-(U1A-RESERVED-Pad7)") (class "Default")
      (node (ref "U1") (pin "7") (pinfunction "RESERVED_7") (pintype "passive+no_connect"))
    )
    (net (code "122") (name "unconnected-(U1A-RESERVED-Pad8)") (class "Default")
      (node (ref "U1") (pin "8") (pinfunction "RESERVED_8") (pintype "passive+no_connect"))
    )
    (net (code "123") (name "unconnected-(U1A-RESERVED-Pad19)") (class "Default")
      (node (ref "U1") (pin "19") (pinfunction "RESERVED_19") (pintype "passive+no_connect"))
    )
    (net (code "124") (name "unconnected-(U1A-RESERVED-Pad21)") (class "Default")
      (node (ref "U1") (pin "21") (pinfunction "RESERVED_21") (pintype "passive+no_connect"))
    )
    (net (code "125") (name "unconnected-(U1A-RESERVED-Pad22)") (class "Default")
      (node (ref "U1") (pin "22") (pinfunction "RESERVED_22") (pintype "passive+no_connect"))
    )
    (net (code "126") (name "unconnected-(U1A-RESERVED-Pad23)") (class "Default")
      (node (ref "U1") (pin "23") (pinfunction "RESERVED_23") (pintype "passive+no_connect"))
    )
    (net (code "127") (name "unconnected-(U1A-RESERVED-Pad25)") (class "Default")
      (node (ref "U1") (pin "25") (pinfunction "RESERVED_25") (pintype "passive+no_connect"))
    )
    (net (code "128") (name "unconnected-(U1A-RESERVED-Pad26)") (class "Default")
      (node (ref "U1") (pin "26") (pinfunction "RESERVED_26") (pintype "passive+no_connect"))
    )
    (net (code "129") (name "unconnected-(U1A-RESERVED-Pad28)") (class "Default")
      (node (ref "U1") (pin "28") (pinfunction "RESERVED_28") (pintype "passive+no_connect"))
    )
    (net (code "130") (name "unconnected-(U1A-RESERVED-Pad29)") (class "Default")
      (node (ref "U1") (pin "29") (pinfunction "RESERVED_29") (pintype "passive+no_connect"))
    )
    (net (code "131") (name "unconnected-(U1A-RESERVED-Pad30)") (class "Default")
      (node (ref "U1") (pin "30") (pinfunction "RESERVED_30") (pintype "passive+no_connect"))
    )
    (net (code "132") (name "unconnected-(U1A-RESERVED-Pad31)") (class "Default")
      (node (ref "U1") (pin "31") (pinfunction "RESERVED_31") (pintype "passive+no_connect"))
    )
    (net (code "133") (name "unconnected-(U1A-RESERVED-Pad32)") (class "Default")
      (node (ref "U1") (pin "32") (pinfunction "RESERVED_32") (pintype "passive+no_connect"))
    )
    (net (code "134") (name "unconnected-(U1A-RESERVED-Pad33)") (class "Default")
      (node (ref "U1") (pin "33") (pinfunction "RESERVED_33") (pintype "passive+no_connect"))
    )
    (net (code "135") (name "unconnected-(U1A-RESERVED-Pad44)") (class "Default")
      (node (ref "U1") (pin "44") (pinfunction "RESERVED_44") (pintype "passive+no_connect"))
    )
    (net (code "136") (name "unconnected-(U2-RA5{slash}~{SS1}-Pad4)") (class "Default")
      (node (ref "U2") (pin "4") (pinfunction "RA5/~{SS1}_4") (pintype "passive"))
    )
    (net (code "137") (name "unconnected-(U3-GND-Pad9)") (class "Default")
      (node (ref "U3") (pin "9") (pinfunction "GND_9") (pintype "passive"))
    )
    (net (code "138") (name "unconnected-(U4-NC-Pad4)") (class "Default")
      (node (ref "U4") (pin "4") (pinfunction "NC_4") (pintype "passive"))
    )
    (net (code "139") (name "unconnected-(U4-NC-Pad5)") (class "Default")
      (node (ref "U4") (pin "5") (pinfunction "NC_5") (pintype "passive"))
    )
    (net (code "140") (name "unconnected-(U4-PAD-Pad0)") (class "Default")
      (node (ref "U4") (pin "0") (pinfunction "PAD_0") (pintype "passive+no_connect"))
    )
    (net (code "141") (name "unconnected-(U5-VSS-Pad9)") (class "Default")
      (node (ref "U5") (pin "9") (pinfunction "VSS_9") (pintype "passive"))
    )
    (net (code "142") (name "unconnected-(U5-nRESET-Pad6)") (class "Default")
      (node (ref "U5") (pin "6") (pinfunction "nRESET_6") (pintype "passive+no_connect"))
    )
  )
)
